# card.net
KiCad netlist of a schematic drawn in EAGLE
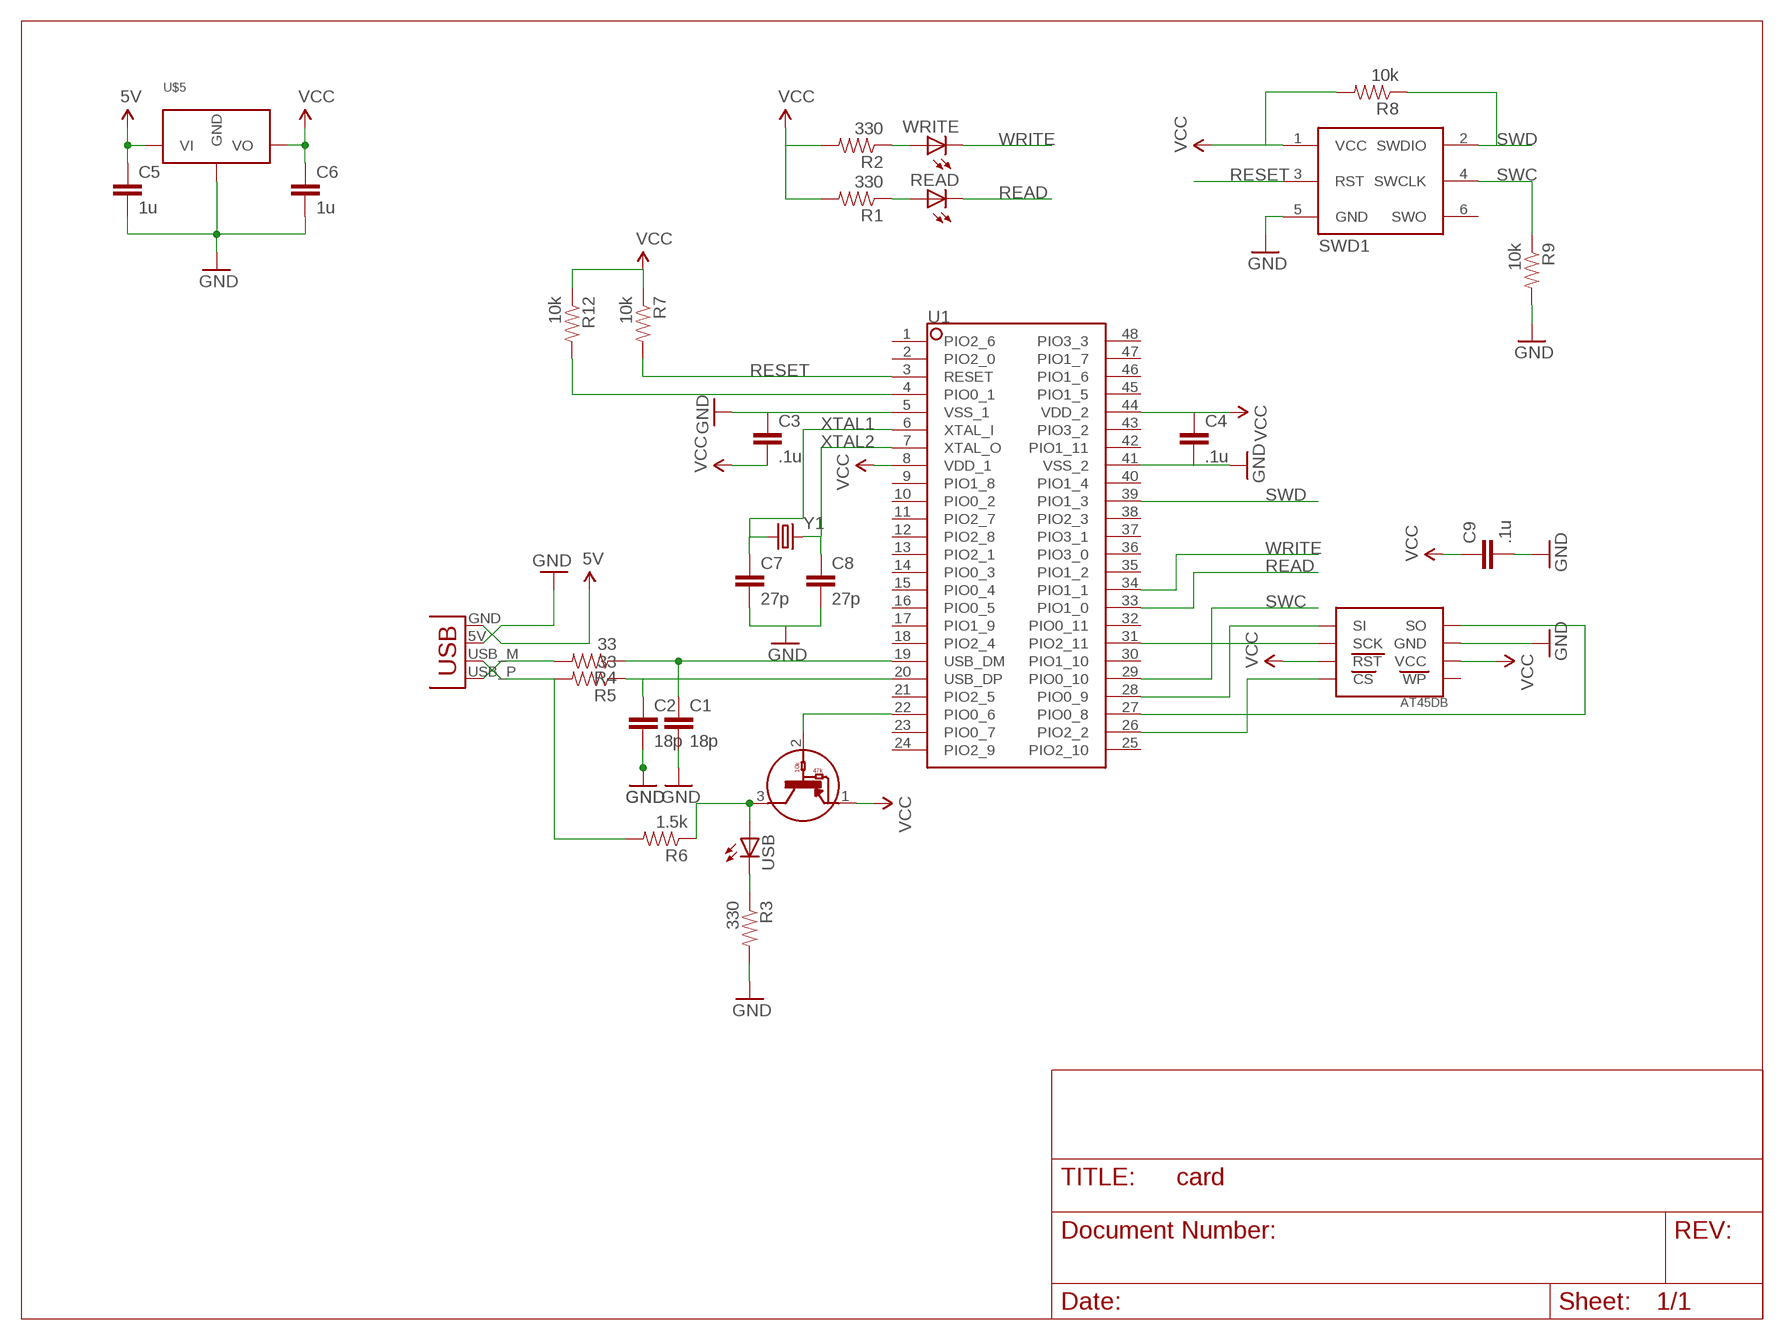
[diagram p0: schematic, sheet 1]

(export (version "E")
  (design (tool "Eeschema 10.0.6"))
  (components
    (comp (ref "AT45DB")
      (value "AT45DBXXXD")
      (footprint "eagle-import:SOIC8")
      (libsource (lib "eagle-import") (part "AT45DBXXXD"))
    )
    (comp (ref "C1")
      (value "18p")
      (footprint "eagle-import:0805")
      (libsource (lib "eagle-import") (part "CAP0805"))
    )
    (comp (ref "C2")
      (value "18p")
      (footprint "eagle-import:0805")
      (libsource (lib "eagle-import") (part "CAP0805"))
    )
    (comp (ref "C3")
      (value ".1u")
      (footprint "eagle-import:1206")
      (libsource (lib "eagle-import") (part "CAP1206"))
    )
    (comp (ref "C4")
      (value ".1u")
      (footprint "eagle-import:1206")
      (libsource (lib "eagle-import") (part "CAP1206"))
    )
    (comp (ref "C5")
      (value "1u")
      (footprint "eagle-import:0805")
      (libsource (lib "eagle-import") (part "CAP0805"))
    )
    (comp (ref "C6")
      (value "1u")
      (footprint "eagle-import:0805")
      (libsource (lib "eagle-import") (part "CAP0805"))
    )
    (comp (ref "C7")
      (value "27p")
      (footprint "eagle-import:0805")
      (libsource (lib "eagle-import") (part "CAP0805"))
    )
    (comp (ref "C8")
      (value "27p")
      (footprint "eagle-import:0805")
      (libsource (lib "eagle-import") (part "CAP0805"))
    )
    (comp (ref "C9")
      (value ".1u")
      (footprint "eagle-import:0805")
      (libsource (lib "eagle-import") (part "CAP0805"))
    )
    (comp (ref "JP1")
      (value "USBPCB")
      (footprint "eagle-import:USB-A-PCB")
      (libsource (lib "eagle-import") (part "USBPCB"))
    )
    (comp (ref "R1")
      (value "330")
      (footprint "eagle-import:0805")
      (libsource (lib "eagle-import") (part "RESISTOR0805-RES"))
    )
    (comp (ref "R2")
      (value "330")
      (footprint "eagle-import:0805")
      (libsource (lib "eagle-import") (part "RESISTOR0805-RES"))
    )
    (comp (ref "R3")
      (value "330")
      (footprint "eagle-import:0805")
      (libsource (lib "eagle-import") (part "RESISTOR0805-RES"))
    )
    (comp (ref "R4")
      (value "33")
      (footprint "eagle-import:0805")
      (libsource (lib "eagle-import") (part "RESISTOR0805-RES"))
    )
    (comp (ref "R5")
      (value "33")
      (footprint "eagle-import:0805")
      (libsource (lib "eagle-import") (part "RESISTOR0805-RES"))
    )
    (comp (ref "R6")
      (value "1.5k")
      (footprint "eagle-import:0805")
      (libsource (lib "eagle-import") (part "RESISTOR0805-RES"))
    )
    (comp (ref "R7")
      (value "10k")
      (footprint "eagle-import:0805")
      (libsource (lib "eagle-import") (part "RESISTOR0805-RES"))
    )
    (comp (ref "R8")
      (value "10k")
      (footprint "eagle-import:0805")
      (libsource (lib "eagle-import") (part "RESISTOR0805-RES"))
    )
    (comp (ref "R9")
      (value "10k")
      (footprint "eagle-import:0805")
      (libsource (lib "eagle-import") (part "RESISTOR0805-RES"))
    )
    (comp (ref "R12")
      (value "10k")
      (footprint "eagle-import:0805")
      (libsource (lib "eagle-import") (part "RESISTOR0805-RES"))
    )
    (comp (ref "READ")
      (value "LED1206")
      (footprint "eagle-import:LED-1206")
      (libsource (lib "eagle-import") (part "LED1206"))
    )
    (comp (ref "SWD1")
      (value "TC2030CTX_NL")
      (footprint "eagle-import:TC2030-NL")
      (libsource (lib "eagle-import") (part "TC2030CTX_NL"))
    )
    (comp (ref "U$5")
      (value "3_3V_REG")
      (footprint "eagle-import:SOT23")
      (libsource (lib "eagle-import") (part "3_3V_REG"))
    )
    (comp (ref "U1")
      (value "LPC1343FBD48")
      (footprint "eagle-import:LQFP48")
      (libsource (lib "eagle-import") (part "LPC1343FBD48"))
    )
    (comp (ref "U3")
      (value "DTA114YKA")
      (footprint "eagle-import:DTA114YKA")
      (libsource (lib "eagle-import") (part "DTA114YKA"))
    )
    (comp (ref "USB")
      (value "LED1206")
      (footprint "eagle-import:LED-1206")
      (libsource (lib "eagle-import") (part "LED1206"))
    )
    (comp (ref "WRITE")
      (value "LED1206")
      (footprint "eagle-import:LED-1206")
      (libsource (lib "eagle-import") (part "LED1206"))
    )
    (comp (ref "Y1")
      (value "CRYSTAL5X3")
      (footprint "eagle-import:CRYSTAL-SMD-5X3")
      (libsource (lib "eagle-import") (part "CRYSTAL5X3"))
    )
  )
  (nets
    (net (code "1") (name "/READ") (class "Default")
      (node (ref "READ") (pin "C") (pinfunction "C_C") (pintype "passive"))
      (node (ref "U1") (pin "33") (pinfunction "PIO1_0_33") (pintype "bidirectional"))
    )
    (net (code "2") (name "/RESET") (class "Default")
      (node (ref "R7") (pin "2") (pinfunction "2_2") (pintype "passive"))
      (node (ref "SWD1") (pin "3") (pinfunction "RST_3") (pintype "bidirectional"))
      (node (ref "U1") (pin "3") (pinfunction "RESET_3") (pintype "bidirectional"))
    )
    (net (code "3") (name "/SWC") (class "Default")
      (node (ref "R9") (pin "1") (pinfunction "1_1") (pintype "passive"))
      (node (ref "SWD1") (pin "4") (pinfunction "SWCLK_4") (pintype "bidirectional"))
      (node (ref "U1") (pin "29") (pinfunction "PIO0_10_29") (pintype "bidirectional"))
    )
    (net (code "4") (name "/SWD") (class "Default")
      (node (ref "R8") (pin "1") (pinfunction "1_1") (pintype "passive"))
      (node (ref "SWD1") (pin "2") (pinfunction "SWDIO_2") (pintype "bidirectional"))
      (node (ref "U1") (pin "39") (pinfunction "PIO1_3_39") (pintype "bidirectional"))
    )
    (net (code "5") (name "/WRITE") (class "Default")
      (node (ref "U1") (pin "34") (pinfunction "PIO1_1_34") (pintype "bidirectional"))
      (node (ref "WRITE") (pin "C") (pinfunction "C_C") (pintype "passive"))
    )
    (net (code "6") (name "/XTAL1") (class "Default")
      (node (ref "C7") (pin "1") (pinfunction "1_1") (pintype "passive"))
      (node (ref "U1") (pin "6") (pinfunction "XTAL_I_6") (pintype "bidirectional"))
      (node (ref "Y1") (pin "1") (pinfunction "1_1") (pintype "passive"))
    )
    (net (code "7") (name "/XTAL2") (class "Default")
      (node (ref "C8") (pin "1") (pinfunction "1_1") (pintype "passive"))
      (node (ref "U1") (pin "7") (pinfunction "XTAL_O_7") (pintype "bidirectional"))
      (node (ref "Y1") (pin "3") (pinfunction "2_3") (pintype "passive"))
    )
    (net (code "8") (name "5V") (class "Default")
      (node (ref "C5") (pin "1") (pinfunction "1_1") (pintype "passive"))
      (node (ref "JP1") (pin "GND") (pinfunction "GND_GND") (pintype "bidirectional"))
      (node (ref "U$5") (pin "1") (pinfunction "VI_1") (pintype "bidirectional"))
    )
    (net (code "9") (name "GND") (class "Default")
      (node (ref "AT45DB") (pin "7") (pinfunction "GND_7") (pintype "bidirectional"))
      (node (ref "C1") (pin "2") (pinfunction "2_2") (pintype "passive"))
      (node (ref "C2") (pin "2") (pinfunction "2_2") (pintype "passive"))
      (node (ref "C3") (pin "1") (pinfunction "1_1") (pintype "passive"))
      (node (ref "C4") (pin "2") (pinfunction "2_2") (pintype "passive"))
      (node (ref "C5") (pin "2") (pinfunction "2_2") (pintype "passive"))
      (node (ref "C6") (pin "2") (pinfunction "2_2") (pintype "passive"))
      (node (ref "C7") (pin "2") (pinfunction "2_2") (pintype "passive"))
      (node (ref "C8") (pin "2") (pinfunction "2_2") (pintype "passive"))
      (node (ref "C9") (pin "2") (pinfunction "2_2") (pintype "passive"))
      (node (ref "JP1") (pin "5V") (pinfunction "VBUS_5V") (pintype "bidirectional"))
      (node (ref "R3") (pin "2") (pinfunction "2_2") (pintype "passive"))
      (node (ref "R9") (pin "2") (pinfunction "2_2") (pintype "passive"))
      (node (ref "SWD1") (pin "5") (pinfunction "GND_5") (pintype "bidirectional"))
      (node (ref "U$5") (pin "3") (pinfunction "GND_3") (pintype "bidirectional"))
      (node (ref "U1") (pin "41") (pinfunction "VSS_2_41") (pintype "bidirectional"))
      (node (ref "U1") (pin "5") (pinfunction "VSS_1_5") (pintype "bidirectional"))
    )
    (net (code "10") (name "Net-(AT45DB-CS)") (class "Default")
      (node (ref "AT45DB") (pin "4") (pinfunction "CS_4") (pintype "bidirectional"))
      (node (ref "U1") (pin "26") (pinfunction "PIO2_2_26") (pintype "bidirectional"))
    )
    (net (code "11") (name "Net-(AT45DB-SCK)") (class "Default")
      (node (ref "AT45DB") (pin "2") (pinfunction "SCK_2") (pintype "bidirectional"))
      (node (ref "U1") (pin "31") (pinfunction "PIO2_11_31") (pintype "bidirectional"))
    )
    (net (code "12") (name "Net-(AT45DB-SI)") (class "Default")
      (node (ref "AT45DB") (pin "1") (pinfunction "SI_1") (pintype "bidirectional"))
      (node (ref "U1") (pin "28") (pinfunction "PIO0_9_28") (pintype "bidirectional"))
    )
    (net (code "13") (name "Net-(AT45DB-SO)") (class "Default")
      (node (ref "AT45DB") (pin "8") (pinfunction "SO_8") (pintype "bidirectional"))
      (node (ref "U1") (pin "27") (pinfunction "PIO0_8_27") (pintype "bidirectional"))
    )
    (net (code "14") (name "Net-(JP1-D+)") (class "Default")
      (node (ref "JP1") (pin "USB_P") (pinfunction "D+_USB_P") (pintype "bidirectional"))
      (node (ref "R4") (pin "2") (pinfunction "2_2") (pintype "passive"))
    )
    (net (code "15") (name "Net-(JP1-D-)") (class "Default")
      (node (ref "JP1") (pin "USB_M") (pinfunction "D-_USB_M") (pintype "bidirectional"))
      (node (ref "R5") (pin "2") (pinfunction "2_2") (pintype "passive"))
      (node (ref "R6") (pin "2") (pinfunction "2_2") (pintype "passive"))
    )
    (net (code "16") (name "Net-(R1-Pad1)") (class "Default")
      (node (ref "R1") (pin "1") (pinfunction "1_1") (pintype "passive"))
      (node (ref "READ") (pin "A") (pinfunction "A_A") (pintype "passive"))
    )
    (net (code "17") (name "Net-(R2-Pad1)") (class "Default")
      (node (ref "R2") (pin "1") (pinfunction "1_1") (pintype "passive"))
      (node (ref "WRITE") (pin "A") (pinfunction "A_A") (pintype "passive"))
    )
    (net (code "18") (name "Net-(R3-Pad1)") (class "Default")
      (node (ref "R3") (pin "1") (pinfunction "1_1") (pintype "passive"))
      (node (ref "USB") (pin "C") (pinfunction "C_C") (pintype "passive"))
    )
    (net (code "19") (name "Net-(U1-PIO0_1)") (class "Default")
      (node (ref "R12") (pin "2") (pinfunction "2_2") (pintype "passive"))
      (node (ref "U1") (pin "4") (pinfunction "PIO0_1_4") (pintype "bidirectional"))
    )
    (net (code "20") (name "Net-(U1-PIO0_6)") (class "Default")
      (node (ref "U1") (pin "22") (pinfunction "PIO0_6_22") (pintype "bidirectional"))
      (node (ref "U3") (pin "2") (pinfunction "P$2_2") (pintype "bidirectional"))
    )
    (net (code "21") (name "Net-(U1-USB_DM)") (class "Default")
      (node (ref "C1") (pin "1") (pinfunction "1_1") (pintype "passive"))
      (node (ref "R4") (pin "1") (pinfunction "1_1") (pintype "passive"))
      (node (ref "U1") (pin "19") (pinfunction "USB_DM_19") (pintype "bidirectional"))
    )
    (net (code "22") (name "Net-(U1-USB_DP)") (class "Default")
      (node (ref "C2") (pin "1") (pinfunction "1_1") (pintype "passive"))
      (node (ref "R5") (pin "1") (pinfunction "1_1") (pintype "passive"))
      (node (ref "U1") (pin "20") (pinfunction "USB_DP_20") (pintype "bidirectional"))
    )
    (net (code "23") (name "Net-(U3-P$3)") (class "Default")
      (node (ref "R6") (pin "1") (pinfunction "1_1") (pintype "passive"))
      (node (ref "U3") (pin "3") (pinfunction "P$3_3") (pintype "bidirectional"))
      (node (ref "USB") (pin "A") (pinfunction "A_A") (pintype "passive"))
    )
    (net (code "24") (name "VCC") (class "Default")
      (node (ref "AT45DB") (pin "3") (pinfunction "RST_3") (pintype "bidirectional"))
      (node (ref "AT45DB") (pin "6") (pinfunction "VCC_6") (pintype "bidirectional"))
      (node (ref "C3") (pin "2") (pinfunction "2_2") (pintype "passive"))
      (node (ref "C4") (pin "1") (pinfunction "1_1") (pintype "passive"))
      (node (ref "C6") (pin "1") (pinfunction "1_1") (pintype "passive"))
      (node (ref "C9") (pin "1") (pinfunction "1_1") (pintype "passive"))
      (node (ref "R1") (pin "2") (pinfunction "2_2") (pintype "passive"))
      (node (ref "R12") (pin "1") (pinfunction "1_1") (pintype "passive"))
      (node (ref "R2") (pin "2") (pinfunction "2_2") (pintype "passive"))
      (node (ref "R7") (pin "1") (pinfunction "1_1") (pintype "passive"))
      (node (ref "R8") (pin "2") (pinfunction "2_2") (pintype "passive"))
      (node (ref "SWD1") (pin "1") (pinfunction "VCC_1") (pintype "bidirectional"))
      (node (ref "U$5") (pin "2") (pinfunction "VO_2") (pintype "bidirectional"))
      (node (ref "U1") (pin "44") (pinfunction "VDD_2_44") (pintype "bidirectional"))
      (node (ref "U1") (pin "8") (pinfunction "VDD_1_8") (pintype "bidirectional"))
      (node (ref "U3") (pin "1") (pinfunction "P$1_1") (pintype "bidirectional"))
    )
    (net (code "25") (name "unconnected-(AT45DB-WP-Pad5)") (class "Default")
      (node (ref "AT45DB") (pin "5") (pinfunction "WP_5") (pintype "bidirectional"))
    )
    (net (code "26") (name "unconnected-(SWD1-SWO-Pad6)") (class "Default")
      (node (ref "SWD1") (pin "6") (pinfunction "SWO_6") (pintype "bidirectional"))
    )
    (net (code "27") (name "unconnected-(U1-PIO0_2-Pad10)") (class "Default")
      (node (ref "U1") (pin "10") (pinfunction "PIO0_2_10") (pintype "bidirectional"))
    )
    (net (code "28") (name "unconnected-(U1-PIO0_3-Pad14)") (class "Default")
      (node (ref "U1") (pin "14") (pinfunction "PIO0_3_14") (pintype "bidirectional"))
    )
    (net (code "29") (name "unconnected-(U1-PIO0_4-Pad15)") (class "Default")
      (node (ref "U1") (pin "15") (pinfunction "PIO0_4_15") (pintype "bidirectional"))
    )
    (net (code "30") (name "unconnected-(U1-PIO0_5-Pad16)") (class "Default")
      (node (ref "U1") (pin "16") (pinfunction "PIO0_5_16") (pintype "bidirectional"))
    )
    (net (code "31") (name "unconnected-(U1-PIO0_7-Pad23)") (class "Default")
      (node (ref "U1") (pin "23") (pinfunction "PIO0_7_23") (pintype "bidirectional"))
    )
    (net (code "32") (name "unconnected-(U1-PIO0_11-Pad32)") (class "Default")
      (node (ref "U1") (pin "32") (pinfunction "PIO0_11_32") (pintype "bidirectional"))
    )
    (net (code "33") (name "unconnected-(U1-PIO1_2-Pad35)") (class "Default")
      (node (ref "U1") (pin "35") (pinfunction "PIO1_2_35") (pintype "bidirectional"))
    )
    (net (code "34") (name "unconnected-(U1-PIO1_4-Pad40)") (class "Default")
      (node (ref "U1") (pin "40") (pinfunction "PIO1_4_40") (pintype "bidirectional"))
    )
    (net (code "35") (name "unconnected-(U1-PIO1_5-Pad45)") (class "Default")
      (node (ref "U1") (pin "45") (pinfunction "PIO1_5_45") (pintype "bidirectional"))
    )
    (net (code "36") (name "unconnected-(U1-PIO1_6-Pad46)") (class "Default")
      (node (ref "U1") (pin "46") (pinfunction "PIO1_6_46") (pintype "bidirectional"))
    )
    (net (code "37") (name "unconnected-(U1-PIO1_7-Pad47)") (class "Default")
      (node (ref "U1") (pin "47") (pinfunction "PIO1_7_47") (pintype "bidirectional"))
    )
    (net (code "38") (name "unconnected-(U1-PIO1_8-Pad9)") (class "Default")
      (node (ref "U1") (pin "9") (pinfunction "PIO1_8_9") (pintype "bidirectional"))
    )
    (net (code "39") (name "unconnected-(U1-PIO1_9-Pad17)") (class "Default")
      (node (ref "U1") (pin "17") (pinfunction "PIO1_9_17") (pintype "bidirectional"))
    )
    (net (code "40") (name "unconnected-(U1-PIO1_10-Pad30)") (class "Default")
      (node (ref "U1") (pin "30") (pinfunction "PIO1_10_30") (pintype "bidirectional"))
    )
    (net (code "41") (name "unconnected-(U1-PIO1_11-Pad42)") (class "Default")
      (node (ref "U1") (pin "42") (pinfunction "PIO1_11_42") (pintype "bidirectional"))
    )
    (net (code "42") (name "unconnected-(U1-PIO2_0-Pad2)") (class "Default")
      (node (ref "U1") (pin "2") (pinfunction "PIO2_0_2") (pintype "bidirectional"))
    )
    (net (code "43") (name "unconnected-(U1-PIO2_1-Pad13)") (class "Default")
      (node (ref "U1") (pin "13") (pinfunction "PIO2_1_13") (pintype "bidirectional"))
    )
    (net (code "44") (name "unconnected-(U1-PIO2_3-Pad38)") (class "Default")
      (node (ref "U1") (pin "38") (pinfunction "PIO2_3_38") (pintype "bidirectional"))
    )
    (net (code "45") (name "unconnected-(U1-PIO2_4-Pad18)") (class "Default")
      (node (ref "U1") (pin "18") (pinfunction "PIO2_4_18") (pintype "bidirectional"))
    )
    (net (code "46") (name "unconnected-(U1-PIO2_5-Pad21)") (class "Default")
      (node (ref "U1") (pin "21") (pinfunction "PIO2_5_21") (pintype "bidirectional"))
    )
    (net (code "47") (name "unconnected-(U1-PIO2_6-Pad1)") (class "Default")
      (node (ref "U1") (pin "1") (pinfunction "PIO2_6_1") (pintype "bidirectional"))
    )
    (net (code "48") (name "unconnected-(U1-PIO2_7-Pad11)") (class "Default")
      (node (ref "U1") (pin "11") (pinfunction "PIO2_7_11") (pintype "bidirectional"))
    )
    (net (code "49") (name "unconnected-(U1-PIO2_8-Pad12)") (class "Default")
      (node (ref "U1") (pin "12") (pinfunction "PIO2_8_12") (pintype "bidirectional"))
    )
    (net (code "50") (name "unconnected-(U1-PIO2_9-Pad24)") (class "Default")
      (node (ref "U1") (pin "24") (pinfunction "PIO2_9_24") (pintype "bidirectional"))
    )
    (net (code "51") (name "unconnected-(U1-PIO2_10-Pad25)") (class "Default")
      (node (ref "U1") (pin "25") (pinfunction "PIO2_10_25") (pintype "bidirectional"))
    )
    (net (code "52") (name "unconnected-(U1-PIO3_0-Pad36)") (class "Default")
      (node (ref "U1") (pin "36") (pinfunction "PIO3_0_36") (pintype "bidirectional"))
    )
    (net (code "53") (name "unconnected-(U1-PIO3_1-Pad37)") (class "Default")
      (node (ref "U1") (pin "37") (pinfunction "PIO3_1_37") (pintype "bidirectional"))
    )
    (net (code "54") (name "unconnected-(U1-PIO3_2-Pad43)") (class "Default")
      (node (ref "U1") (pin "43") (pinfunction "PIO3_2_43") (pintype "bidirectional"))
    )
    (net (code "55") (name "unconnected-(U1-PIO3_3-Pad48)") (class "Default")
      (node (ref "U1") (pin "48") (pinfunction "PIO3_3_48") (pintype "bidirectional"))
    )
  )
)
